# p2mini-001.net
KiCad netlist of a schematic drawn in EAGLE
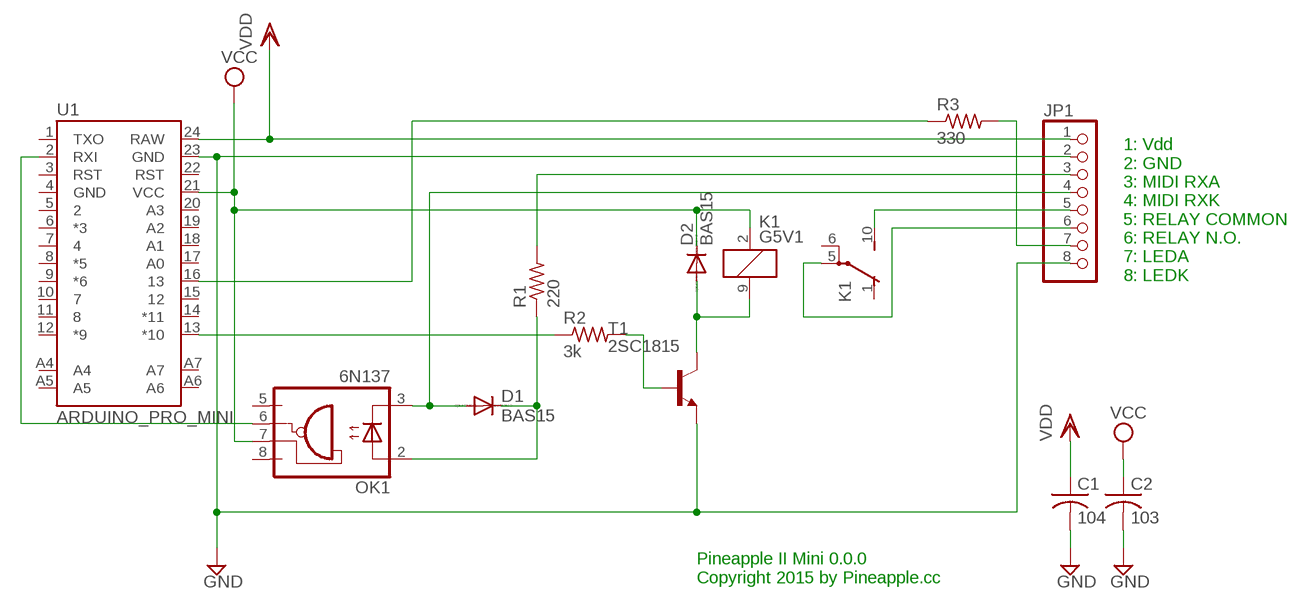
[diagram p0: schematic, sheet 1]

(export (version "E")
  (design (tool "Eeschema 10.0.6"))
  (components
    (comp (ref "C1")
      (value "104")
      (footprint "eagle-import:C025-025X050")
      (libsource (lib "eagle-import") (part "C-US025-025X050"))
    )
    (comp (ref "C2")
      (value "103")
      (footprint "eagle-import:C025-025X050")
      (libsource (lib "eagle-import") (part "C-US025-025X050"))
    )
    (comp (ref "D1")
      (value "BAS15")
      (footprint "eagle-import:DO34-7")
      (libsource (lib "eagle-import") (part "BAS15"))
    )
    (comp (ref "D2")
      (value "BAS15")
      (footprint "eagle-import:DO34-7")
      (libsource (lib "eagle-import") (part "BAS15"))
    )
    (comp (ref "JP1")
      (value "PINHD-1X8")
      (footprint "eagle-import:1X08")
      (libsource (lib "eagle-import") (part "PINHD-1X8"))
    )
    (comp (ref "K1")
      (value "G5V1")
      (footprint "eagle-import:G5V1")
      (fields (field (name "MPN") "G5V-1-DC24"))
      (libsource (lib "eagle-import") (part "G5V1"))
    )
    (comp (ref "OK1")
      (value "6N137")
      (footprint "eagle-import:DIL08")
      (libsource (lib "eagle-import") (part "6N137"))
    )
    (comp (ref "R1")
      (value "220")
      (footprint "eagle-import:0204_5")
      (libsource (lib "eagle-import") (part "R-US_0204/5"))
    )
    (comp (ref "R2")
      (value "3k")
      (footprint "eagle-import:0204_5")
      (libsource (lib "eagle-import") (part "R-US_0204/5"))
    )
    (comp (ref "R3")
      (value "330")
      (footprint "eagle-import:0204_5")
      (libsource (lib "eagle-import") (part "R-US_0204/5"))
    )
    (comp (ref "T1")
      (value "2SC1815")
      (footprint "eagle-import:TO92-ECB")
      (libsource (lib "eagle-import") (part "2SC1815"))
    )
    (comp (ref "U1")
      (value "ARDUINO_PRO_MINI")
      (footprint "eagle-import:ARDUINO_PRO_MINI")
      (libsource (lib "eagle-import") (part "ARDUINO_PRO_MINI"))
    )
  )
  (nets
    (net (code "1") (name "GND") (class "Default")
      (node (ref "C1") (pin "2") (pinfunction "2_2") (pintype "passive"))
      (node (ref "C2") (pin "2") (pinfunction "2_2") (pintype "passive"))
      (node (ref "JP1") (pin "2") (pinfunction "2_2") (pintype "passive"))
      (node (ref "JP1") (pin "8") (pinfunction "8_8") (pintype "passive"))
      (node (ref "T1") (pin "E") (pinfunction "E_E") (pintype "passive"))
      (node (ref "U1") (pin "23") (pinfunction "GND_23") (pintype "bidirectional"))
    )
    (net (code "2") (name "Net-(JP1-Pad3)") (class "Default")
      (node (ref "JP1") (pin "3") (pinfunction "3_3") (pintype "passive"))
      (node (ref "R1") (pin "2") (pinfunction "2_2") (pintype "passive"))
    )
    (net (code "3") (name "Net-(JP1-Pad6)") (class "Default")
      (node (ref "JP1") (pin "6") (pinfunction "6_6") (pintype "passive"))
      (node (ref "K1") (pin "5") (pinfunction "P_5") (pintype "passive"))
    )
    (net (code "4") (name "Net-(JP1-Pad7)") (class "Default")
      (node (ref "JP1") (pin "7") (pinfunction "7_7") (pintype "passive"))
      (node (ref "R3") (pin "2") (pinfunction "2_2") (pintype "passive"))
    )
    (net (code "5") (name "Net-(K1A-2)") (class "Default")
      (node (ref "D2") (pin "A") (pinfunction "A_A") (pintype "passive"))
      (node (ref "K1") (pin "9") (pinfunction "2_9") (pintype "passive"))
      (node (ref "T1") (pin "C") (pinfunction "C_C") (pintype "passive"))
    )
    (net (code "6") (name "Net-(K1B-S)") (class "Default")
      (node (ref "JP1") (pin "5") (pinfunction "5_5") (pintype "passive"))
      (node (ref "K1") (pin "10") (pinfunction "S_10") (pintype "passive"))
    )
    (net (code "7") (name "Net-(OK1-A)") (class "Default")
      (node (ref "D1") (pin "C") (pinfunction "C_C") (pintype "passive"))
      (node (ref "OK1") (pin "2") (pinfunction "A_2") (pintype "passive"))
      (node (ref "R1") (pin "1") (pinfunction "1_1") (pintype "passive"))
    )
    (net (code "8") (name "Net-(OK1-C)") (class "Default")
      (node (ref "D1") (pin "A") (pinfunction "A_A") (pintype "passive"))
      (node (ref "JP1") (pin "4") (pinfunction "4_4") (pintype "passive"))
      (node (ref "OK1") (pin "3") (pinfunction "C_3") (pintype "passive"))
    )
    (net (code "9") (name "Net-(OK1-VO)") (class "Default")
      (node (ref "OK1") (pin "6") (pinfunction "VO_6") (pintype "passive"))
      (node (ref "U1") (pin "2") (pinfunction "RXI_2") (pintype "bidirectional"))
    )
    (net (code "10") (name "Net-(R2-Pad2)") (class "Default")
      (node (ref "R2") (pin "2") (pinfunction "2_2") (pintype "passive"))
      (node (ref "T1") (pin "B") (pinfunction "B_B") (pintype "passive"))
    )
    (net (code "11") (name "Net-(U1-*10)") (class "Default")
      (node (ref "R2") (pin "1") (pinfunction "1_1") (pintype "passive"))
      (node (ref "U1") (pin "13") (pinfunction "*10_13") (pintype "bidirectional"))
    )
    (net (code "12") (name "Net-(U1-13)") (class "Default")
      (node (ref "R3") (pin "1") (pinfunction "1_1") (pintype "passive"))
      (node (ref "U1") (pin "16") (pinfunction "13_16") (pintype "bidirectional"))
    )
    (net (code "13") (name "VCC") (class "Default")
      (node (ref "C2") (pin "1") (pinfunction "1_1") (pintype "passive"))
      (node (ref "D2") (pin "C") (pinfunction "C_C") (pintype "passive"))
      (node (ref "K1") (pin "2") (pinfunction "1_2") (pintype "passive"))
      (node (ref "OK1") (pin "7") (pinfunction "VE_7") (pintype "passive"))
      (node (ref "U1") (pin "21") (pinfunction "VCC_21") (pintype "bidirectional"))
    )
    (net (code "14") (name "VDD") (class "Default")
      (node (ref "C1") (pin "1") (pinfunction "1_1") (pintype "passive"))
      (node (ref "JP1") (pin "1") (pinfunction "1_1") (pintype "passive"))
      (node (ref "U1") (pin "24") (pinfunction "RAW_24") (pintype "bidirectional"))
    )
    (net (code "15") (name "unconnected-(K1B-O-Pad1)") (class "Default")
      (node (ref "K1") (pin "1") (pinfunction "O_1") (pintype "passive"))
    )
    (net (code "16") (name "unconnected-(K1B-P-Pad6)") (class "Default")
      (node (ref "K1") (pin "6") (pinfunction "P_6") (pintype "passive"))
    )
    (net (code "17") (name "unconnected-(OK1-GND-Pad5)") (class "Default")
      (node (ref "OK1") (pin "5") (pinfunction "GND_5") (pintype "passive"))
    )
    (net (code "18") (name "unconnected-(OK1-VCC-Pad8)") (class "Default")
      (node (ref "OK1") (pin "8") (pinfunction "VCC_8") (pintype "passive"))
    )
    (net (code "19") (name "unconnected-(U1-*3-Pad6)") (class "Default")
      (node (ref "U1") (pin "6") (pinfunction "*3_6") (pintype "bidirectional"))
    )
    (net (code "20") (name "unconnected-(U1-*5-Pad8)") (class "Default")
      (node (ref "U1") (pin "8") (pinfunction "*5_8") (pintype "bidirectional"))
    )
    (net (code "21") (name "unconnected-(U1-*6-Pad9)") (class "Default")
      (node (ref "U1") (pin "9") (pinfunction "*6_9") (pintype "bidirectional"))
    )
    (net (code "22") (name "unconnected-(U1-*9-Pad12)") (class "Default")
      (node (ref "U1") (pin "12") (pinfunction "*9_12") (pintype "bidirectional"))
    )
    (net (code "23") (name "unconnected-(U1-*11-Pad14)") (class "Default")
      (node (ref "U1") (pin "14") (pinfunction "*11_14") (pintype "bidirectional"))
    )
    (net (code "24") (name "unconnected-(U1-2-Pad5)") (class "Default")
      (node (ref "U1") (pin "5") (pinfunction "2_5") (pintype "bidirectional"))
    )
    (net (code "25") (name "unconnected-(U1-4-Pad7)") (class "Default")
      (node (ref "U1") (pin "7") (pinfunction "4_7") (pintype "bidirectional"))
    )
    (net (code "26") (name "unconnected-(U1-7-Pad10)") (class "Default")
      (node (ref "U1") (pin "10") (pinfunction "7_10") (pintype "bidirectional"))
    )
    (net (code "27") (name "unconnected-(U1-8-Pad11)") (class "Default")
      (node (ref "U1") (pin "11") (pinfunction "8_11") (pintype "bidirectional"))
    )
    (net (code "28") (name "unconnected-(U1-12-Pad15)") (class "Default")
      (node (ref "U1") (pin "15") (pinfunction "12_15") (pintype "bidirectional"))
    )
    (net (code "29") (name "unconnected-(U1-A0-Pad17)") (class "Default")
      (node (ref "U1") (pin "17") (pinfunction "A0_17") (pintype "bidirectional"))
    )
    (net (code "30") (name "unconnected-(U1-A1-Pad18)") (class "Default")
      (node (ref "U1") (pin "18") (pinfunction "A1_18") (pintype "bidirectional"))
    )
    (net (code "31") (name "unconnected-(U1-A2-Pad19)") (class "Default")
      (node (ref "U1") (pin "19") (pinfunction "A2_19") (pintype "bidirectional"))
    )
    (net (code "32") (name "unconnected-(U1-A3-Pad20)") (class "Default")
      (node (ref "U1") (pin "20") (pinfunction "A3_20") (pintype "bidirectional"))
    )
    (net (code "33") (name "unconnected-(U1-GND-Pad4)") (class "Default")
      (node (ref "U1") (pin "4") (pinfunction "GND_4") (pintype "bidirectional"))
    )
    (net (code "34") (name "unconnected-(U1-PadA4)") (class "Default")
      (node (ref "U1") (pin "A4") (pinfunction "A4_A4") (pintype "bidirectional"))
    )
    (net (code "35") (name "unconnected-(U1-PadA5)") (class "Default")
      (node (ref "U1") (pin "A5") (pinfunction "A5_A5") (pintype "bidirectional"))
    )
    (net (code "36") (name "unconnected-(U1-PadA6)") (class "Default")
      (node (ref "U1") (pin "A6") (pinfunction "A6_A6") (pintype "bidirectional"))
    )
    (net (code "37") (name "unconnected-(U1-PadA7)") (class "Default")
      (node (ref "U1") (pin "A7") (pinfunction "A7_A7") (pintype "bidirectional"))
    )
    (net (code "38") (name "unconnected-(U1-RST-Pad3)") (class "Default")
      (node (ref "U1") (pin "3") (pinfunction "RST_3") (pintype "bidirectional"))
    )
    (net (code "39") (name "unconnected-(U1-RST-Pad22)") (class "Default")
      (node (ref "U1") (pin "22") (pinfunction "RST_22") (pintype "bidirectional"))
    )
    (net (code "40") (name "unconnected-(U1-TXO-Pad1)") (class "Default")
      (node (ref "U1") (pin "1") (pinfunction "TXO_1") (pintype "bidirectional"))
    )
  )
)
